# Selector.net
KiCad netlist of a schematic drawn in Altium Designer
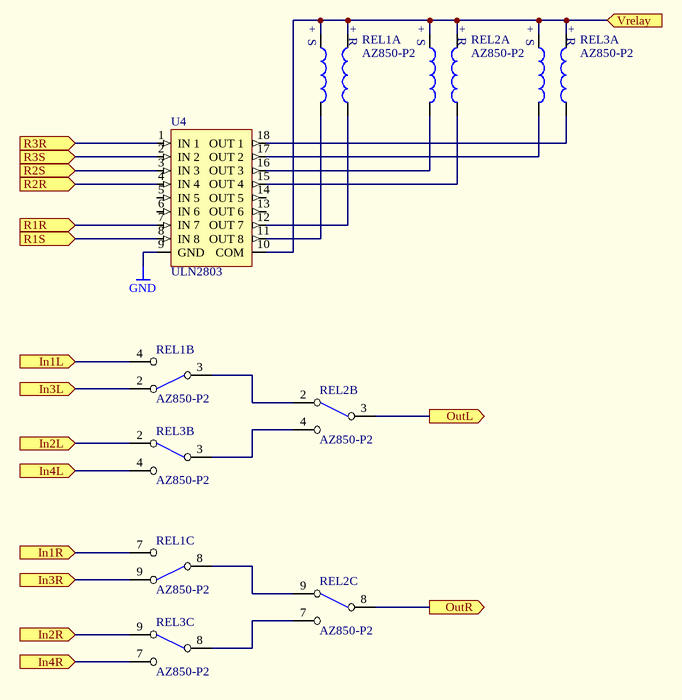
[diagram p0: Selector.SchDoc]

(export (version "E")
  (design (tool "Eeschema 10.0.6"))
  (components
    (comp (ref "REL1")
      (value "AZ850-P2")
      (footprint "RELAY_AZ850")
      (description "bi-stable relay")
      (libsource (lib "") (part "AZ850-P2_2"))
    )
    (comp (ref "REL2")
      (value "AZ850-P2")
      (footprint "RELAY_AZ850")
      (description "bi-stable relay")
      (libsource (lib "MainSchlib") (part "AZ850-P2"))
    )
    (comp (ref "REL3")
      (value "AZ850-P2")
      (footprint "RELAY_AZ850")
      (description "bi-stable relay")
      (libsource (lib "MainSchlib") (part "AZ850-P2"))
    )
    (comp (ref "U4")
      (value "ULN2803")
      (footprint "IC_SOIC-18")
      (description "HIGH-VOLTAGE,HIGH-CURRENT DARLINTON ARRAYS")
      (libsource (lib "MainSchlib") (part "ULN2803"))
    )
  )
  (nets
    (net (code "1") (name "/In1L") (class "Default")
      (node (ref "REL1") (pin "4") (pinfunction "4_4") (pintype "passive"))
    )
    (net (code "2") (name "/In1R") (class "Default")
      (node (ref "REL1") (pin "7") (pinfunction "7_7") (pintype "passive"))
    )
    (net (code "3") (name "/In2L") (class "Default")
      (node (ref "REL3") (pin "2") (pinfunction "2_2") (pintype "passive"))
    )
    (net (code "4") (name "/In2R") (class "Default")
      (node (ref "REL3") (pin "9") (pinfunction "9_9") (pintype "passive"))
    )
    (net (code "5") (name "/In3L") (class "Default")
      (node (ref "REL1") (pin "2") (pinfunction "2_2") (pintype "passive"))
    )
    (net (code "6") (name "/In3R") (class "Default")
      (node (ref "REL1") (pin "9") (pinfunction "9_9") (pintype "passive"))
    )
    (net (code "7") (name "/In4L") (class "Default")
      (node (ref "REL3") (pin "4") (pinfunction "4_4") (pintype "passive"))
    )
    (net (code "8") (name "/In4R") (class "Default")
      (node (ref "REL3") (pin "7") (pinfunction "7_7") (pintype "passive"))
    )
    (net (code "9") (name "/OutL") (class "Default")
      (node (ref "REL2") (pin "3") (pinfunction "3_3") (pintype "passive"))
    )
    (net (code "10") (name "/OutR") (class "Default")
      (node (ref "REL2") (pin "8") (pinfunction "8_8") (pintype "passive"))
    )
    (net (code "11") (name "/R1R") (class "Default")
      (node (ref "U4") (pin "7") (pinfunction "IN_7_7") (pintype "input"))
    )
    (net (code "12") (name "/R1S") (class "Default")
      (node (ref "U4") (pin "8") (pinfunction "IN_8_8") (pintype "input"))
    )
    (net (code "13") (name "/R2R") (class "Default")
      (node (ref "U4") (pin "4") (pinfunction "IN_4_4") (pintype "input"))
    )
    (net (code "14") (name "/R2S") (class "Default")
      (node (ref "U4") (pin "3") (pinfunction "IN_3_3") (pintype "input"))
    )
    (net (code "15") (name "/R3R") (class "Default")
      (node (ref "U4") (pin "1") (pinfunction "IN_1_1") (pintype "input"))
    )
    (net (code "16") (name "/R3S") (class "Default")
      (node (ref "U4") (pin "2") (pinfunction "IN_2_2") (pintype "input"))
    )
    (net (code "17") (name "/Vrelay") (class "Default")
      (node (ref "REL1") (pin "1") (pinfunction "1_1") (pintype "passive"))
      (node (ref "REL1") (pin "10") (pinfunction "10_10") (pintype "passive"))
      (node (ref "REL2") (pin "1") (pinfunction "1_1") (pintype "passive"))
      (node (ref "REL2") (pin "10") (pinfunction "10_10") (pintype "passive"))
      (node (ref "REL3") (pin "1") (pinfunction "1_1") (pintype "passive"))
      (node (ref "REL3") (pin "10") (pinfunction "10_10") (pintype "passive"))
      (node (ref "U4") (pin "10") (pinfunction "COM_10") (pintype "passive"))
    )
    (net (code "18") (name "GND") (class "Default")
      (node (ref "U4") (pin "9") (pinfunction "GND_9") (pintype "power_in"))
    )
    (net (code "19") (name "Net-(REL1-Pad3)") (class "Default")
      (node (ref "REL1") (pin "3") (pinfunction "3_3") (pintype "passive"))
      (node (ref "REL2") (pin "2") (pinfunction "2_2") (pintype "passive"))
    )
    (net (code "20") (name "Net-(REL1-Pad8)") (class "Default")
      (node (ref "REL1") (pin "8") (pinfunction "8_8") (pintype "passive"))
      (node (ref "REL2") (pin "9") (pinfunction "9_9") (pintype "passive"))
    )
    (net (code "21") (name "Net-(REL2-Pad4)") (class "Default")
      (node (ref "REL2") (pin "4") (pinfunction "4_4") (pintype "passive"))
      (node (ref "REL3") (pin "3") (pinfunction "3_3") (pintype "passive"))
    )
    (net (code "22") (name "Net-(REL2-Pad7)") (class "Default")
      (node (ref "REL2") (pin "7") (pinfunction "7_7") (pintype "passive"))
      (node (ref "REL3") (pin "8") (pinfunction "8_8") (pintype "passive"))
    )
    (net (code "23") (name "Net-(U4-OUT_1)") (class "Default")
      (node (ref "REL3") (pin "6") (pinfunction "6_6") (pintype "passive"))
      (node (ref "U4") (pin "18") (pinfunction "OUT_1_18") (pintype "output"))
    )
    (net (code "24") (name "Net-(U4-OUT_2)") (class "Default")
      (node (ref "REL3") (pin "5") (pinfunction "5_5") (pintype "passive"))
      (node (ref "U4") (pin "17") (pinfunction "OUT_2_17") (pintype "output"))
    )
    (net (code "25") (name "Net-(U4-OUT_3)") (class "Default")
      (node (ref "REL2") (pin "5") (pinfunction "5_5") (pintype "passive"))
      (node (ref "U4") (pin "16") (pinfunction "OUT_3_16") (pintype "output"))
    )
    (net (code "26") (name "Net-(U4-OUT_4)") (class "Default")
      (node (ref "REL2") (pin "6") (pinfunction "6_6") (pintype "passive"))
      (node (ref "U4") (pin "15") (pinfunction "OUT_4_15") (pintype "output"))
    )
    (net (code "27") (name "Net-(U4-OUT_7)") (class "Default")
      (node (ref "REL1") (pin "6") (pinfunction "6_6") (pintype "passive"))
      (node (ref "U4") (pin "12") (pinfunction "OUT_7_12") (pintype "output"))
    )
    (net (code "28") (name "Net-(U4-OUT_8)") (class "Default")
      (node (ref "REL1") (pin "5") (pinfunction "5_5") (pintype "passive"))
      (node (ref "U4") (pin "11") (pinfunction "OUT_8_11") (pintype "output"))
    )
    (net (code "29") (name "unconnected-(U4-IN_5-Pad5)") (class "Default")
      (node (ref "U4") (pin "5") (pinfunction "IN_5_5") (pintype "input"))
    )
    (net (code "30") (name "unconnected-(U4-IN_6-Pad6)") (class "Default")
      (node (ref "U4") (pin "6") (pinfunction "IN_6_6") (pintype "input"))
    )
    (net (code "31") (name "unconnected-(U4-OUT_5-Pad14)") (class "Default")
      (node (ref "U4") (pin "14") (pinfunction "OUT_5_14") (pintype "output"))
    )
    (net (code "32") (name "unconnected-(U4-OUT_6-Pad13)") (class "Default")
      (node (ref "U4") (pin "13") (pinfunction "OUT_6_13") (pintype "output"))
    )
  )
)
